# QFN10_2x2.net
KiCad netlist of a schematic drawn in EAGLE
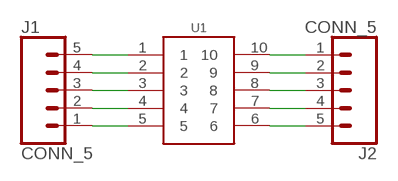
[diagram p0: schematic, sheet 1]

(export (version "E")
  (design (tool "Eeschema 10.0.6"))
  (components
    (comp (ref "J1")
      (value "CONN_5")
      (footprint "eagle-import:1X05")
      (libsource (lib "eagle-import") (part "CONN_5"))
    )
    (comp (ref "J2")
      (value "CONN_5")
      (footprint "eagle-import:1X05")
      (libsource (lib "eagle-import") (part "CONN_5"))
    )
    (comp (ref "U1")
      (value "GEN_10QFN10_2X2")
      (footprint "eagle-import:QFN10_SI114X")
      (libsource (lib "eagle-import") (part "GEN_10QFN10_2X2"))
    )
  )
  (nets
    (net (code "1") (name "Net-(J1-Pad1)") (class "Default")
      (node (ref "J1") (pin "1") (pinfunction "1_1") (pintype "passive"))
      (node (ref "U1") (pin "5") (pinfunction "5_5") (pintype "bidirectional"))
    )
    (net (code "2") (name "Net-(J1-Pad2)") (class "Default")
      (node (ref "J1") (pin "2") (pinfunction "2_2") (pintype "passive"))
      (node (ref "U1") (pin "4") (pinfunction "4_4") (pintype "bidirectional"))
    )
    (net (code "3") (name "Net-(J1-Pad3)") (class "Default")
      (node (ref "J1") (pin "3") (pinfunction "3_3") (pintype "passive"))
      (node (ref "U1") (pin "3") (pinfunction "3_3") (pintype "bidirectional"))
    )
    (net (code "4") (name "Net-(J1-Pad4)") (class "Default")
      (node (ref "J1") (pin "4") (pinfunction "4_4") (pintype "passive"))
      (node (ref "U1") (pin "2") (pinfunction "2_2") (pintype "bidirectional"))
    )
    (net (code "5") (name "Net-(J1-Pad5)") (class "Default")
      (node (ref "J1") (pin "5") (pinfunction "5_5") (pintype "passive"))
      (node (ref "U1") (pin "1") (pinfunction "1_1") (pintype "bidirectional"))
    )
    (net (code "6") (name "Net-(J2-Pad1)") (class "Default")
      (node (ref "J2") (pin "1") (pinfunction "1_1") (pintype "passive"))
      (node (ref "U1") (pin "10") (pinfunction "10_10") (pintype "bidirectional"))
    )
    (net (code "7") (name "Net-(J2-Pad2)") (class "Default")
      (node (ref "J2") (pin "2") (pinfunction "2_2") (pintype "passive"))
      (node (ref "U1") (pin "9") (pinfunction "9_9") (pintype "bidirectional"))
    )
    (net (code "8") (name "Net-(J2-Pad3)") (class "Default")
      (node (ref "J2") (pin "3") (pinfunction "3_3") (pintype "passive"))
      (node (ref "U1") (pin "8") (pinfunction "8_8") (pintype "bidirectional"))
    )
    (net (code "9") (name "Net-(J2-Pad4)") (class "Default")
      (node (ref "J2") (pin "4") (pinfunction "4_4") (pintype "passive"))
      (node (ref "U1") (pin "7") (pinfunction "7_7") (pintype "bidirectional"))
    )
    (net (code "10") (name "Net-(J2-Pad5)") (class "Default")
      (node (ref "J2") (pin "5") (pinfunction "5_5") (pintype "passive"))
      (node (ref "U1") (pin "6") (pinfunction "6_6") (pintype "bidirectional"))
    )
  )
)
